# headstageNano.net
KiCad netlist of a schematic drawn in EAGLE
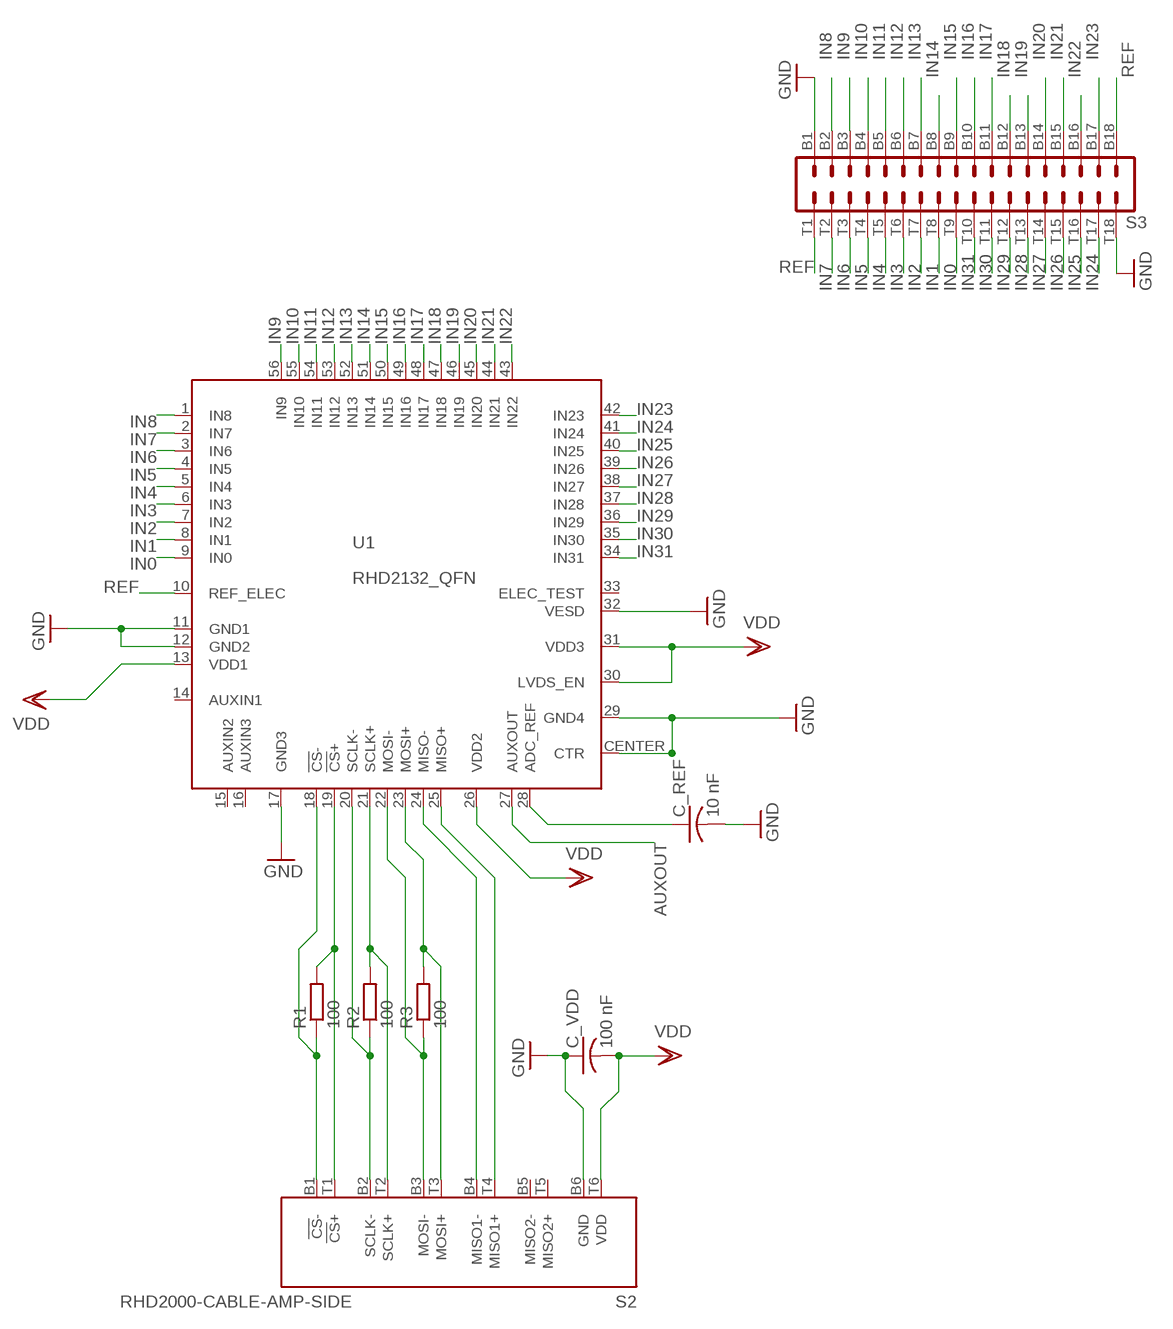
[diagram p0: schematic, sheet 1]

(export (version "E")
  (design (tool "Eeschema 10.0.6"))
  (components
    (comp (ref "C_REF")
      (value "10 nF")
      (footprint "eagle-import:C0402K")
      (libsource (lib "eagle-import") (part "C-USC0402K"))
    )
    (comp (ref "C_VDD")
      (value "100 nF")
      (footprint "eagle-import:C0402K")
      (libsource (lib "eagle-import") (part "C-USC0402K"))
    )
    (comp (ref "R1")
      (value "100")
      (footprint "eagle-import:R0402")
      (libsource (lib "eagle-import") (part "R-EU_R0402"))
    )
    (comp (ref "R2")
      (value "100")
      (footprint "eagle-import:R0402")
      (libsource (lib "eagle-import") (part "R-EU_R0402"))
    )
    (comp (ref "R3")
      (value "100")
      (footprint "eagle-import:R0402")
      (libsource (lib "eagle-import") (part "R-EU_R0402"))
    )
    (comp (ref "S2")
      (value "RHD2000-CABLE-AMP-SIDE")
      (footprint "eagle-import:OMNETICS_PZN-12-AA")
      (libsource (lib "eagle-import") (part "RHD2000-CABLE-AMP-SIDE"))
    )
    (comp (ref "S3")
      (value "OMNETICS_A79025")
      (footprint "eagle-import:OMNETICS_A79025")
      (libsource (lib "eagle-import") (part "OMNETICS_A79025"))
    )
    (comp (ref "U1")
      (value "RHD2132_QFN")
      (footprint "eagle-import:QFN56_8_X_8_LARGE")
      (libsource (lib "eagle-import") (part "RHD2132_QFN"))
    )
  )
  (nets
    (net (code "1") (name "/AUXOUT") (class "Default")
      (node (ref "U1") (pin "27") (pinfunction "AUXOUT_27") (pintype "tri_state"))
    )
    (net (code "2") (name "/IN0") (class "Default")
      (node (ref "S3") (pin "T9") (pinfunction "T9_T9") (pintype "passive"))
      (node (ref "U1") (pin "9") (pinfunction "IN0_9") (pintype "input"))
    )
    (net (code "3") (name "/IN1") (class "Default")
      (node (ref "S3") (pin "T8") (pinfunction "T8_T8") (pintype "passive"))
      (node (ref "U1") (pin "8") (pinfunction "IN1_8") (pintype "input"))
    )
    (net (code "4") (name "/IN2") (class "Default")
      (node (ref "S3") (pin "T7") (pinfunction "T7_T7") (pintype "passive"))
      (node (ref "U1") (pin "7") (pinfunction "IN2_7") (pintype "input"))
    )
    (net (code "5") (name "/IN3") (class "Default")
      (node (ref "S3") (pin "T6") (pinfunction "T6_T6") (pintype "passive"))
      (node (ref "U1") (pin "6") (pinfunction "IN3_6") (pintype "input"))
    )
    (net (code "6") (name "/IN4") (class "Default")
      (node (ref "S3") (pin "T5") (pinfunction "T5_T5") (pintype "passive"))
      (node (ref "U1") (pin "5") (pinfunction "IN4_5") (pintype "input"))
    )
    (net (code "7") (name "/IN5") (class "Default")
      (node (ref "S3") (pin "T4") (pinfunction "T4_T4") (pintype "passive"))
      (node (ref "U1") (pin "4") (pinfunction "IN5_4") (pintype "input"))
    )
    (net (code "8") (name "/IN6") (class "Default")
      (node (ref "S3") (pin "T3") (pinfunction "T3_T3") (pintype "passive"))
      (node (ref "U1") (pin "3") (pinfunction "IN6_3") (pintype "input"))
    )
    (net (code "9") (name "/IN7") (class "Default")
      (node (ref "S3") (pin "T2") (pinfunction "T2_T2") (pintype "passive"))
      (node (ref "U1") (pin "2") (pinfunction "IN7_2") (pintype "input"))
    )
    (net (code "10") (name "/IN8") (class "Default")
      (node (ref "S3") (pin "B2") (pinfunction "B2_B2") (pintype "passive"))
      (node (ref "U1") (pin "1") (pinfunction "IN8_1") (pintype "input"))
    )
    (net (code "11") (name "/IN9") (class "Default")
      (node (ref "S3") (pin "B3") (pinfunction "B3_B3") (pintype "passive"))
      (node (ref "U1") (pin "56") (pinfunction "IN9_56") (pintype "input"))
    )
    (net (code "12") (name "/IN10") (class "Default")
      (node (ref "S3") (pin "B4") (pinfunction "B4_B4") (pintype "passive"))
      (node (ref "U1") (pin "55") (pinfunction "IN10_55") (pintype "input"))
    )
    (net (code "13") (name "/IN11") (class "Default")
      (node (ref "S3") (pin "B5") (pinfunction "B5_B5") (pintype "passive"))
      (node (ref "U1") (pin "54") (pinfunction "IN11_54") (pintype "input"))
    )
    (net (code "14") (name "/IN12") (class "Default")
      (node (ref "S3") (pin "B6") (pinfunction "B6_B6") (pintype "passive"))
      (node (ref "U1") (pin "53") (pinfunction "IN12_53") (pintype "input"))
    )
    (net (code "15") (name "/IN13") (class "Default")
      (node (ref "S3") (pin "B7") (pinfunction "B7_B7") (pintype "passive"))
      (node (ref "U1") (pin "52") (pinfunction "IN13_52") (pintype "input"))
    )
    (net (code "16") (name "/IN14") (class "Default")
      (node (ref "S3") (pin "B8") (pinfunction "B8_B8") (pintype "passive"))
      (node (ref "U1") (pin "51") (pinfunction "IN14_51") (pintype "input"))
    )
    (net (code "17") (name "/IN15") (class "Default")
      (node (ref "S3") (pin "B9") (pinfunction "B9_B9") (pintype "passive"))
      (node (ref "U1") (pin "50") (pinfunction "IN15_50") (pintype "input"))
    )
    (net (code "18") (name "/IN16") (class "Default")
      (node (ref "S3") (pin "B10") (pinfunction "B10_B10") (pintype "passive"))
      (node (ref "U1") (pin "49") (pinfunction "IN16_49") (pintype "input"))
    )
    (net (code "19") (name "/IN17") (class "Default")
      (node (ref "S3") (pin "B11") (pinfunction "B11_B11") (pintype "passive"))
      (node (ref "U1") (pin "48") (pinfunction "IN17_48") (pintype "input"))
    )
    (net (code "20") (name "/IN18") (class "Default")
      (node (ref "S3") (pin "B12") (pinfunction "B12_B12") (pintype "passive"))
      (node (ref "U1") (pin "47") (pinfunction "IN18_47") (pintype "input"))
    )
    (net (code "21") (name "/IN19") (class "Default")
      (node (ref "S3") (pin "B13") (pinfunction "B13_B13") (pintype "passive"))
      (node (ref "U1") (pin "46") (pinfunction "IN19_46") (pintype "input"))
    )
    (net (code "22") (name "/IN20") (class "Default")
      (node (ref "S3") (pin "B14") (pinfunction "B14_B14") (pintype "passive"))
      (node (ref "U1") (pin "45") (pinfunction "IN20_45") (pintype "input"))
    )
    (net (code "23") (name "/IN21") (class "Default")
      (node (ref "S3") (pin "B15") (pinfunction "B15_B15") (pintype "passive"))
      (node (ref "U1") (pin "44") (pinfunction "IN21_44") (pintype "input"))
    )
    (net (code "24") (name "/IN22") (class "Default")
      (node (ref "S3") (pin "B16") (pinfunction "B16_B16") (pintype "passive"))
      (node (ref "U1") (pin "43") (pinfunction "IN22_43") (pintype "input"))
    )
    (net (code "25") (name "/IN23") (class "Default")
      (node (ref "S3") (pin "B17") (pinfunction "B17_B17") (pintype "passive"))
      (node (ref "U1") (pin "42") (pinfunction "IN23_42") (pintype "input"))
    )
    (net (code "26") (name "/IN24") (class "Default")
      (node (ref "S3") (pin "T17") (pinfunction "T17_T17") (pintype "passive"))
      (node (ref "U1") (pin "41") (pinfunction "IN24_41") (pintype "input"))
    )
    (net (code "27") (name "/IN25") (class "Default")
      (node (ref "S3") (pin "T16") (pinfunction "T16_T16") (pintype "passive"))
      (node (ref "U1") (pin "40") (pinfunction "IN25_40") (pintype "input"))
    )
    (net (code "28") (name "/IN26") (class "Default")
      (node (ref "S3") (pin "T15") (pinfunction "T15_T15") (pintype "passive"))
      (node (ref "U1") (pin "39") (pinfunction "IN26_39") (pintype "input"))
    )
    (net (code "29") (name "/IN27") (class "Default")
      (node (ref "S3") (pin "T14") (pinfunction "T14_T14") (pintype "passive"))
      (node (ref "U1") (pin "38") (pinfunction "IN27_38") (pintype "input"))
    )
    (net (code "30") (name "/IN28") (class "Default")
      (node (ref "S3") (pin "T13") (pinfunction "T13_T13") (pintype "passive"))
      (node (ref "U1") (pin "37") (pinfunction "IN28_37") (pintype "input"))
    )
    (net (code "31") (name "/IN29") (class "Default")
      (node (ref "S3") (pin "T12") (pinfunction "T12_T12") (pintype "passive"))
      (node (ref "U1") (pin "36") (pinfunction "IN29_36") (pintype "input"))
    )
    (net (code "32") (name "/IN30") (class "Default")
      (node (ref "S3") (pin "T11") (pinfunction "T11_T11") (pintype "passive"))
      (node (ref "U1") (pin "35") (pinfunction "IN30_35") (pintype "input"))
    )
    (net (code "33") (name "/IN31") (class "Default")
      (node (ref "S3") (pin "T10") (pinfunction "T10_T10") (pintype "passive"))
      (node (ref "U1") (pin "34") (pinfunction "IN31_34") (pintype "input"))
    )
    (net (code "34") (name "/REF") (class "Default")
      (node (ref "S3") (pin "B18") (pinfunction "B18_B18") (pintype "passive"))
      (node (ref "S3") (pin "T1") (pinfunction "T1_T1") (pintype "passive"))
      (node (ref "U1") (pin "10") (pinfunction "REF_ELEC_10") (pintype "input"))
    )
    (net (code "35") (name "GND") (class "Default")
      (node (ref "C_REF") (pin "2") (pinfunction "2_2") (pintype "passive"))
      (node (ref "C_VDD") (pin "1") (pinfunction "1_1") (pintype "passive"))
      (node (ref "S2") (pin "B6") (pinfunction "GND_B6") (pintype "power_in"))
      (node (ref "S3") (pin "B1") (pinfunction "B1_B1") (pintype "passive"))
      (node (ref "S3") (pin "T18") (pinfunction "T18_T18") (pintype "passive"))
      (node (ref "U1") (pin "11") (pinfunction "GND1_11") (pintype "power_in"))
      (node (ref "U1") (pin "12") (pinfunction "GND2_12") (pintype "power_in"))
      (node (ref "U1") (pin "17") (pinfunction "GND3_17") (pintype "power_in"))
      (node (ref "U1") (pin "29") (pinfunction "GND4_29") (pintype "power_in"))
      (node (ref "U1") (pin "32") (pinfunction "VESD_32") (pintype "power_in"))
      (node (ref "U1") (pin "CENTER") (pinfunction "CTR_CENTER") (pintype "power_in"))
    )
    (net (code "36") (name "Net-(S2-MISO1+)") (class "Default")
      (node (ref "S2") (pin "T4") (pinfunction "MISO1+_T4") (pintype "bidirectional"))
      (node (ref "U1") (pin "25") (pinfunction "MISO+_25") (pintype "output"))
    )
    (net (code "37") (name "Net-(S2-MISO1-)") (class "Default")
      (node (ref "S2") (pin "B4") (pinfunction "MISO1-_B4") (pintype "bidirectional"))
      (node (ref "U1") (pin "24") (pinfunction "MISO-_24") (pintype "output"))
    )
    (net (code "38") (name "Net-(S2-MOSI+)") (class "Default")
      (node (ref "R3") (pin "2") (pinfunction "2_2") (pintype "passive"))
      (node (ref "S2") (pin "T3") (pinfunction "MOSI+_T3") (pintype "bidirectional"))
      (node (ref "U1") (pin "23") (pinfunction "MOSI+_23") (pintype "input"))
    )
    (net (code "39") (name "Net-(S2-MOSI-)") (class "Default")
      (node (ref "R3") (pin "1") (pinfunction "1_1") (pintype "passive"))
      (node (ref "S2") (pin "B3") (pinfunction "MOSI-_B3") (pintype "bidirectional"))
      (node (ref "U1") (pin "22") (pinfunction "MOSI-_22") (pintype "input"))
    )
    (net (code "40") (name "Net-(S2-SCLK+)") (class "Default")
      (node (ref "R2") (pin "2") (pinfunction "2_2") (pintype "passive"))
      (node (ref "S2") (pin "T2") (pinfunction "SCLK+_T2") (pintype "bidirectional"))
      (node (ref "U1") (pin "21") (pinfunction "SCLK+_21") (pintype "input"))
    )
    (net (code "41") (name "Net-(S2-SCLK-)") (class "Default")
      (node (ref "R2") (pin "1") (pinfunction "1_1") (pintype "passive"))
      (node (ref "S2") (pin "B2") (pinfunction "SCLK-_B2") (pintype "bidirectional"))
      (node (ref "U1") (pin "20") (pinfunction "SCLK-_20") (pintype "input"))
    )
    (net (code "42") (name "Net-(S2-~{CS}+)") (class "Default")
      (node (ref "R1") (pin "2") (pinfunction "2_2") (pintype "passive"))
      (node (ref "S2") (pin "T1") (pinfunction "~{CS}+_T1") (pintype "bidirectional"))
      (node (ref "U1") (pin "19") (pinfunction "~{CS}+_19") (pintype "input"))
    )
    (net (code "43") (name "Net-(S2-~{CS}-)") (class "Default")
      (node (ref "R1") (pin "1") (pinfunction "1_1") (pintype "passive"))
      (node (ref "S2") (pin "B1") (pinfunction "~{CS}-_B1") (pintype "bidirectional"))
      (node (ref "U1") (pin "18") (pinfunction "~{CS}-_18") (pintype "input"))
    )
    (net (code "44") (name "Net-(U1-ADC_REF)") (class "Default")
      (node (ref "C_REF") (pin "1") (pinfunction "1_1") (pintype "passive"))
      (node (ref "U1") (pin "28") (pinfunction "ADC_REF_28") (pintype "passive"))
    )
    (net (code "45") (name "VDD") (class "Default")
      (node (ref "C_VDD") (pin "2") (pinfunction "2_2") (pintype "passive"))
      (node (ref "S2") (pin "T6") (pinfunction "VDD_T6") (pintype "bidirectional"))
      (node (ref "U1") (pin "13") (pinfunction "VDD1_13") (pintype "power_in"))
      (node (ref "U1") (pin "26") (pinfunction "VDD2_26") (pintype "power_in"))
      (node (ref "U1") (pin "30") (pinfunction "LVDS_EN_30") (pintype "input"))
      (node (ref "U1") (pin "31") (pinfunction "VDD3_31") (pintype "power_in"))
    )
    (net (code "46") (name "unconnected-(S2-MISO2+-PadT5)") (class "Default")
      (node (ref "S2") (pin "T5") (pinfunction "MISO2+_T5") (pintype "bidirectional"))
    )
    (net (code "47") (name "unconnected-(S2-MISO2--PadB5)") (class "Default")
      (node (ref "S2") (pin "B5") (pinfunction "MISO2-_B5") (pintype "bidirectional"))
    )
    (net (code "48") (name "unconnected-(U1-AUXIN1-Pad14)") (class "Default")
      (node (ref "U1") (pin "14") (pinfunction "AUXIN1_14") (pintype "input"))
    )
    (net (code "49") (name "unconnected-(U1-AUXIN2-Pad15)") (class "Default")
      (node (ref "U1") (pin "15") (pinfunction "AUXIN2_15") (pintype "input"))
    )
    (net (code "50") (name "unconnected-(U1-AUXIN3-Pad16)") (class "Default")
      (node (ref "U1") (pin "16") (pinfunction "AUXIN3_16") (pintype "input"))
    )
    (net (code "51") (name "unconnected-(U1-ELEC_TEST-Pad33)") (class "Default")
      (node (ref "U1") (pin "33") (pinfunction "ELEC_TEST_33") (pintype "input"))
    )
  )
)
